# pmic_tps65263_buck.net
KiCad netlist of a schematic drawn in Altium Designer
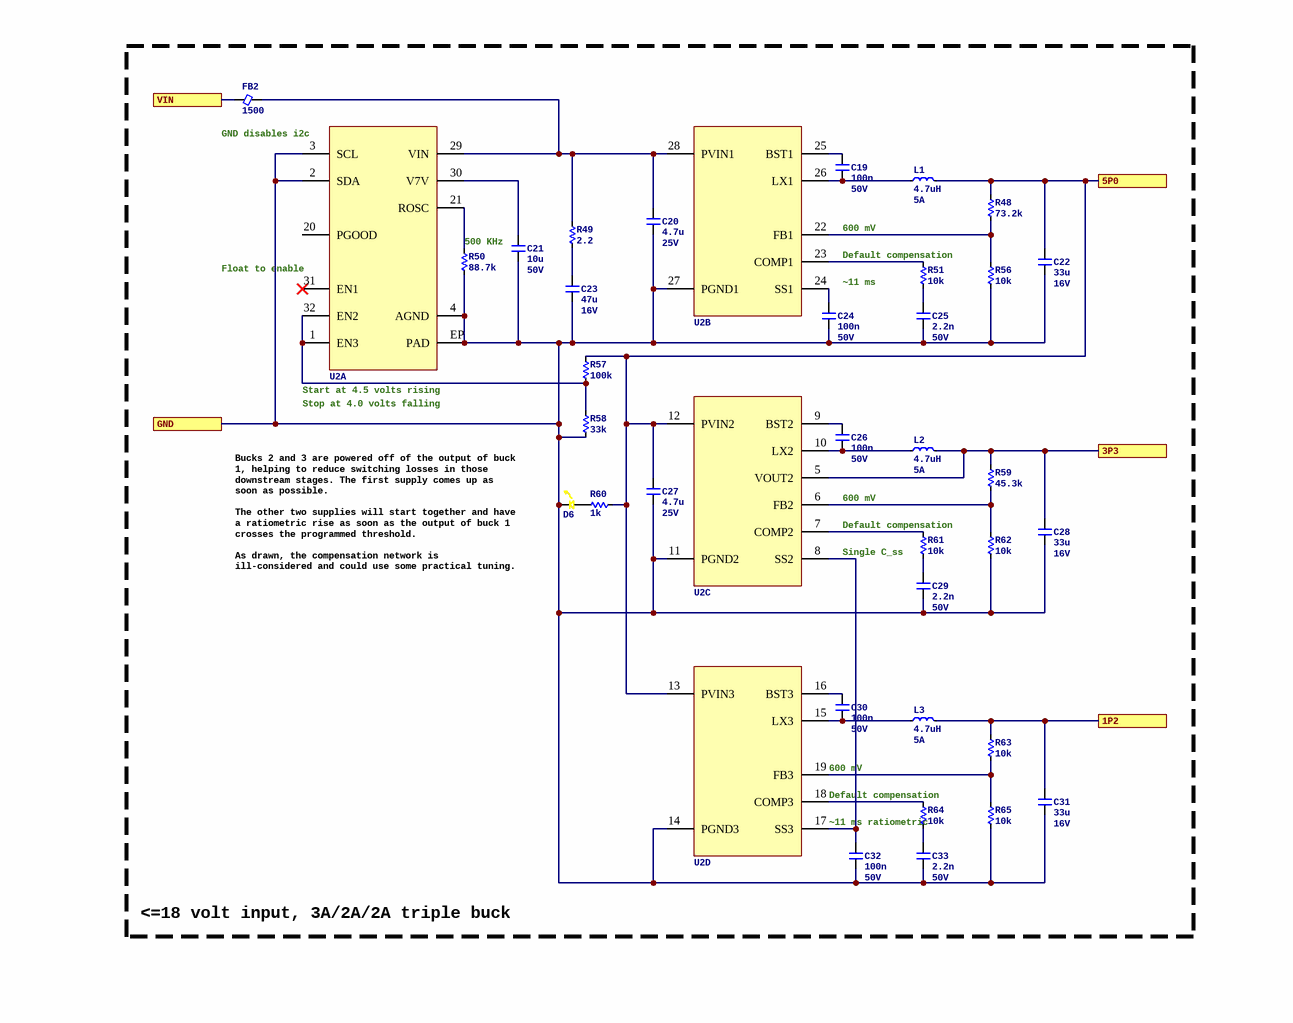
[diagram p0: pmic_tps65263_buck.SchDoc]

(export (version "E")
  (design (tool "Eeschema 10.0.6"))
  (components
    (comp (ref "C19")
      (value "CL05B104KB54PNC")
      (footprint "C0402")
      (fields
        (field (name "CAPACITANCE") "100n")
        (field (name "MANUFACTURER") "Samsung Electro-Mechanics")
        (field (name "VOLTAGE RATING") "50V")
      )
      (libsource (lib "database") (part "__template_cap"))
    )
    (comp (ref "C20")
      (value "CL21B475KAFNNNE")
      (footprint "C0805")
      (fields
        (field (name "CAPACITANCE") "4.7u")
        (field (name "MANUFACTURER") "Samsung Electro-Mechanics")
        (field (name "VOLTAGE RATING") "25V")
      )
      (libsource (lib "database") (part "__template_cap"))
    )
    (comp (ref "C21")
      (value "CL31B106KBHNNNE")
      (footprint "C1206")
      (fields
        (field (name "CAPACITANCE") "10u")
        (field (name "MANUFACTURER") "Samsung Electro-Mechanics")
        (field (name "VOLTAGE RATING") "50V")
      )
      (libsource (lib "database") (part "__template_cap"))
    )
    (comp (ref "C22")
      (value "C4532X7R1C336MT000N")
      (footprint "C1812")
      (fields
        (field (name "CAPACITANCE") "33u")
        (field (name "MANUFACTURER") "TDK")
        (field (name "VOLTAGE RATING") "16V")
      )
      (libsource (lib "database") (part "__template_cap"))
    )
    (comp (ref "C23")
      (value "CGA9N3X7R1C476MT0Y0N")
      (footprint "C2220")
      (fields
        (field (name "CAPACITANCE") "47u")
        (field (name "MANUFACTURER") "TDK")
        (field (name "VOLTAGE RATING") "16V")
      )
      (libsource (lib "database") (part "__template_cap"))
    )
    (comp (ref "C24")
      (value "CL05B104KB54PNC")
      (footprint "C0402")
      (fields
        (field (name "CAPACITANCE") "100n")
        (field (name "MANUFACTURER") "Samsung Electro-Mechanics")
        (field (name "VOLTAGE RATING") "50V")
      )
      (libsource (lib "database") (part "__template_cap"))
    )
    (comp (ref "C25")
      (value "GRM1555C1H222GA01D")
      (footprint "C0402")
      (fields
        (field (name "CAPACITANCE") "2.2n")
        (field (name "MANUFACTURER") "Murata Electronics")
        (field (name "VOLTAGE RATING") "50V")
      )
      (libsource (lib "database") (part "__template_cap"))
    )
    (comp (ref "C26")
      (value "CL05B104KB54PNC")
      (footprint "C0402")
      (fields
        (field (name "CAPACITANCE") "100n")
        (field (name "MANUFACTURER") "Samsung Electro-Mechanics")
        (field (name "VOLTAGE RATING") "50V")
      )
      (libsource (lib "database") (part "__template_cap"))
    )
    (comp (ref "C27")
      (value "CL21B475KAFNNNE")
      (footprint "C0805")
      (fields
        (field (name "CAPACITANCE") "4.7u")
        (field (name "MANUFACTURER") "Samsung Electro-Mechanics")
        (field (name "VOLTAGE RATING") "25V")
      )
      (libsource (lib "database") (part "__template_cap"))
    )
    (comp (ref "C28")
      (value "C4532X7R1C336MT000N")
      (footprint "C1812")
      (fields
        (field (name "CAPACITANCE") "33u")
        (field (name "MANUFACTURER") "TDK")
        (field (name "VOLTAGE RATING") "16V")
      )
      (libsource (lib "database") (part "__template_cap"))
    )
    (comp (ref "C29")
      (value "GRM1555C1H222GA01D")
      (footprint "C0402")
      (fields
        (field (name "CAPACITANCE") "2.2n")
        (field (name "MANUFACTURER") "Murata Electronics")
        (field (name "VOLTAGE RATING") "50V")
      )
      (libsource (lib "database") (part "__template_cap"))
    )
    (comp (ref "C30")
      (value "CL05B104KB54PNC")
      (footprint "C0402")
      (fields
        (field (name "CAPACITANCE") "100n")
        (field (name "MANUFACTURER") "Samsung Electro-Mechanics")
        (field (name "VOLTAGE RATING") "50V")
      )
      (libsource (lib "database") (part "__template_cap"))
    )
    (comp (ref "C31")
      (value "C4532X7R1C336MT000N")
      (footprint "C1812")
      (fields
        (field (name "CAPACITANCE") "33u")
        (field (name "MANUFACTURER") "TDK")
        (field (name "VOLTAGE RATING") "16V")
      )
      (libsource (lib "database") (part "__template_cap"))
    )
    (comp (ref "C32")
      (value "CL05B104KB54PNC")
      (footprint "C0402")
      (fields
        (field (name "CAPACITANCE") "100n")
        (field (name "MANUFACTURER") "Samsung Electro-Mechanics")
        (field (name "VOLTAGE RATING") "50V")
      )
      (libsource (lib "database") (part "__template_cap"))
    )
    (comp (ref "C33")
      (value "GRM1555C1H222GA01D")
      (footprint "C0402")
      (fields
        (field (name "CAPACITANCE") "2.2n")
        (field (name "MANUFACTURER") "Murata Electronics")
        (field (name "VOLTAGE RATING") "50V")
      )
      (libsource (lib "database") (part "__template_cap"))
    )
    (comp (ref "D6")
      (value "LTST-C190YKT")
      (footprint "LED_0603P_YELLOW")
      (description "LED YELLOW CLEAR 0603 SMD")
      (fields (field (name "MANUFACTURER") "Lite-On Inc"))
      (libsource (lib "SSCP") (part "LED_0603_YELLOW_LTST-C190YKT"))
    )
    (comp (ref "FB2")
      (value "MPZ2012S102AT000")
      (footprint "FB0805")
      (fields (field (name "CURRENT RATING (MA)") "1500") (field (name "MANUFACTURER") "TDK"))
      (libsource (lib "database") (part "__template_fb"))
    )
    (comp (ref "L1")
      (value "4.7uH")
      (footprint "SMD-4.1x4.1x2.0")
      (description "5A 4.7uH 6.3A 58mΩ ±20% SMD,4.1x4.1mm Fixed Inductors RoHS")
      (fields
        (field (name "MANUFACTURER PART NUMBER") "FTC404020S4R7MGCA")
        (field (name "MANUFACTURER") "cjiang")
        (field (name "CURRENT") "5A")
      )
      (libsource (lib "SSCP") (part "IND_4.7UH_FTC404020S4R7MGCA"))
    )
    (comp (ref "L2")
      (value "4.7uH")
      (footprint "SMD-4.1x4.1x2.0")
      (description "5A 4.7uH 6.3A 58mΩ ±20% SMD,4.1x4.1mm Fixed Inductors RoHS")
      (fields
        (field (name "MANUFACTURER PART NUMBER") "FTC404020S4R7MGCA")
        (field (name "MANUFACTURER") "cjiang")
        (field (name "CURRENT") "5A")
      )
      (libsource (lib "SSCP") (part "IND_4.7UH_FTC404020S4R7MGCA"))
    )
    (comp (ref "L3")
      (value "4.7uH")
      (footprint "SMD-4.1x4.1x2.0")
      (description "5A 4.7uH 6.3A 58mΩ ±20% SMD,4.1x4.1mm Fixed Inductors RoHS")
      (fields
        (field (name "MANUFACTURER PART NUMBER") "FTC404020S4R7MGCA")
        (field (name "MANUFACTURER") "cjiang")
        (field (name "CURRENT") "5A")
      )
      (libsource (lib "SSCP") (part "IND_4.7UH_FTC404020S4R7MGCA"))
    )
    (comp (ref "R48")
      (value "73.2k")
      (footprint "R0402")
      (fields
        (field (name "TOLERANCE") "1%")
        (field (name "MANUFACTURER PART NUMBER") "0402WGF7322TCE")
        (field (name "MANUFACTURER") "UNI-ROYAL(Uniroyal Elec)")
      )
      (libsource (lib "database") (part "__template_resistor"))
    )
    (comp (ref "R49")
      (value "2.2")
      (footprint "R0805")
      (fields
        (field (name "TOLERANCE") "1%")
        (field (name "MANUFACTURER PART NUMBER") "HP05W3F220KT5E")
        (field (name "MANUFACTURER") "UNI-ROYAL(Uniroyal Elec)")
      )
      (libsource (lib "database") (part "__template_resistor"))
    )
    (comp (ref "R50")
      (value "88.7k")
      (footprint "R0402")
      (fields
        (field (name "TOLERANCE") "1%")
        (field (name "MANUFACTURER PART NUMBER") "0402WGF8872TCE")
        (field (name "MANUFACTURER") "UNI-ROYAL(Uniroyal Elec)")
      )
      (libsource (lib "database") (part "__template_resistor"))
    )
    (comp (ref "R51")
      (value "10k")
      (footprint "R0402")
      (fields
        (field (name "TOLERANCE") "1%")
        (field (name "MANUFACTURER PART NUMBER") "0402WGF1002TCE")
        (field (name "MANUFACTURER") "UNI-ROYAL(Uniroyal Elec)")
      )
      (libsource (lib "database") (part "__template_resistor"))
    )
    (comp (ref "R56")
      (value "10k")
      (footprint "R0402")
      (fields
        (field (name "TOLERANCE") "1%")
        (field (name "MANUFACTURER PART NUMBER") "0402WGF1002TCE")
        (field (name "MANUFACTURER") "UNI-ROYAL(Uniroyal Elec)")
      )
      (libsource (lib "database") (part "__template_resistor"))
    )
    (comp (ref "R57")
      (value "100k")
      (footprint "R0402")
      (fields
        (field (name "TOLERANCE") "1%")
        (field (name "MANUFACTURER PART NUMBER") "0402WGF1003TCE")
        (field (name "MANUFACTURER") "UNI-ROYAL(Uniroyal Elec)")
      )
      (libsource (lib "database") (part "__template_resistor"))
    )
    (comp (ref "R58")
      (value "33k")
      (footprint "R0402")
      (fields
        (field (name "TOLERANCE") "1%")
        (field (name "MANUFACTURER PART NUMBER") "0402WGF3302TCE")
        (field (name "MANUFACTURER") "UNI-ROYAL(Uniroyal Elec)")
      )
      (libsource (lib "database") (part "__template_resistor"))
    )
    (comp (ref "R59")
      (value "45.3k")
      (footprint "R0402")
      (fields
        (field (name "TOLERANCE") "1%")
        (field (name "MANUFACTURER PART NUMBER") "FRC0402F4532TS")
        (field (name "MANUFACTURER") "FOJAN")
      )
      (libsource (lib "database") (part "__template_resistor"))
    )
    (comp (ref "R60")
      (value "1k")
      (footprint "R0402")
      (fields
        (field (name "TOLERANCE") "1%")
        (field (name "MANUFACTURER PART NUMBER") "0402WGF1001TCE")
        (field (name "MANUFACTURER") "UNI-ROYAL(Uniroyal Elec)")
      )
      (libsource (lib "database") (part "__template_resistor"))
    )
    (comp (ref "R61")
      (value "10k")
      (footprint "R0402")
      (fields
        (field (name "TOLERANCE") "1%")
        (field (name "MANUFACTURER PART NUMBER") "0402WGF1002TCE")
        (field (name "MANUFACTURER") "UNI-ROYAL(Uniroyal Elec)")
      )
      (libsource (lib "database") (part "__template_resistor"))
    )
    (comp (ref "R62")
      (value "10k")
      (footprint "R0402")
      (fields
        (field (name "TOLERANCE") "1%")
        (field (name "MANUFACTURER PART NUMBER") "0402WGF1002TCE")
        (field (name "MANUFACTURER") "UNI-ROYAL(Uniroyal Elec)")
      )
      (libsource (lib "database") (part "__template_resistor"))
    )
    (comp (ref "R63")
      (value "10k")
      (footprint "R0402")
      (fields
        (field (name "TOLERANCE") "1%")
        (field (name "MANUFACTURER PART NUMBER") "0402WGF1002TCE")
        (field (name "MANUFACTURER") "UNI-ROYAL(Uniroyal Elec)")
      )
      (libsource (lib "database") (part "__template_resistor"))
    )
    (comp (ref "R64")
      (value "10k")
      (footprint "R0402")
      (fields
        (field (name "TOLERANCE") "1%")
        (field (name "MANUFACTURER PART NUMBER") "0402WGF1002TCE")
        (field (name "MANUFACTURER") "UNI-ROYAL(Uniroyal Elec)")
      )
      (libsource (lib "database") (part "__template_resistor"))
    )
    (comp (ref "R65")
      (value "10k")
      (footprint "R0402")
      (fields
        (field (name "TOLERANCE") "1%")
        (field (name "MANUFACTURER PART NUMBER") "0402WGF1002TCE")
        (field (name "MANUFACTURER") "UNI-ROYAL(Uniroyal Elec)")
      )
      (libsource (lib "database") (part "__template_resistor"))
    )
    (comp (ref "U2")
      (value "TPS65263QRHBRQ1")
      (footprint "TI_RHB")
      (description "Switching Regulator, Current-mode, 3A, 2300kHz Switching Freq-Max, PQCC32")
      (fields (field (name "MANUFACTURER") "Texas Instruments"))
      (libsource (lib "SSCP") (part "BUCK_TPS65263QRHBRQ1"))
    )
  )
  (nets
    (net (code "1") (name "/1P2") (class "Default")
      (node (ref "C31") (pin "1") (pintype "passive"))
      (node (ref "L3") (pin "2") (pintype "passive"))
      (node (ref "R63") (pin "2") (pintype "passive"))
    )
    (net (code "2") (name "/3P3") (class "Default")
      (node (ref "C28") (pin "1") (pintype "passive"))
      (node (ref "L2") (pin "2") (pintype "passive"))
      (node (ref "R59") (pin "2") (pintype "passive"))
      (node (ref "U2") (pin "5") (pinfunction "VOUT2_5") (pintype "passive"))
    )
    (net (code "3") (name "/5P0") (class "Default")
      (node (ref "C22") (pin "1") (pintype "passive"))
      (node (ref "C27") (pin "1") (pintype "passive"))
      (node (ref "L1") (pin "2") (pintype "passive"))
      (node (ref "R48") (pin "2") (pintype "passive"))
      (node (ref "R57") (pin "2") (pintype "passive"))
      (node (ref "R60") (pin "2") (pintype "passive"))
      (node (ref "U2") (pin "12") (pinfunction "PVIN2_12") (pintype "passive"))
      (node (ref "U2") (pin "13") (pinfunction "PVIN3_13") (pintype "passive"))
    )
    (net (code "4") (name "/GND") (class "Default")
      (node (ref "C20") (pin "2") (pintype "passive"))
      (node (ref "C21") (pin "2") (pintype "passive"))
      (node (ref "C22") (pin "2") (pintype "passive"))
      (node (ref "C23") (pin "2") (pintype "passive"))
      (node (ref "C24") (pin "2") (pintype "passive"))
      (node (ref "C25") (pin "2") (pintype "passive"))
      (node (ref "C27") (pin "2") (pintype "passive"))
      (node (ref "C28") (pin "2") (pintype "passive"))
      (node (ref "C29") (pin "2") (pintype "passive"))
      (node (ref "C31") (pin "2") (pintype "passive"))
      (node (ref "C32") (pin "2") (pintype "passive"))
      (node (ref "C33") (pin "2") (pintype "passive"))
      (node (ref "D6") (pin "1") (pintype "passive"))
      (node (ref "R50") (pin "1") (pintype "passive"))
      (node (ref "R56") (pin "1") (pintype "passive"))
      (node (ref "R58") (pin "1") (pintype "passive"))
      (node (ref "R62") (pin "1") (pintype "passive"))
      (node (ref "R65") (pin "1") (pintype "passive"))
      (node (ref "U2") (pin "11") (pinfunction "PGND2_11") (pintype "passive"))
      (node (ref "U2") (pin "14") (pinfunction "PGND3_14") (pintype "passive"))
      (node (ref "U2") (pin "2") (pinfunction "SDA_2") (pintype "passive"))
      (node (ref "U2") (pin "27") (pinfunction "PGND1_27") (pintype "passive"))
      (node (ref "U2") (pin "3") (pinfunction "SCL_3") (pintype "passive"))
      (node (ref "U2") (pin "4") (pinfunction "AGND_4") (pintype "passive"))
      (node (ref "U2") (pin "EP") (pinfunction "PAD_EP") (pintype "passive"))
    )
    (net (code "5") (name "/VIN") (class "Default") (node (ref "FB2") (pin "1") (pintype "passive")))
    (net (code "6") (name "Net-(C23-Pad1)") (class "Default")
      (node (ref "C23") (pin "1") (pintype "passive"))
      (node (ref "R49") (pin "1") (pintype "passive"))
    )
    (net (code "7") (name "Net-(C25-Pad1)") (class "Default")
      (node (ref "C25") (pin "1") (pintype "passive"))
      (node (ref "R51") (pin "1") (pintype "passive"))
    )
    (net (code "8") (name "Net-(C29-Pad1)") (class "Default")
      (node (ref "C29") (pin "1") (pintype "passive"))
      (node (ref "R61") (pin "1") (pintype "passive"))
    )
    (net (code "9") (name "Net-(C33-Pad1)") (class "Default")
      (node (ref "C33") (pin "1") (pintype "passive"))
      (node (ref "R64") (pin "1") (pintype "passive"))
    )
    (net (code "10") (name "Net-(D6-Pad2)") (class "Default")
      (node (ref "D6") (pin "2") (pintype "passive"))
      (node (ref "R60") (pin "1") (pintype "passive"))
    )
    (net (code "11") (name "Net-(U2A-EN2)") (class "Default")
      (node (ref "R57") (pin "1") (pintype "passive"))
      (node (ref "R58") (pin "2") (pintype "passive"))
      (node (ref "U2") (pin "1") (pinfunction "EN3_1") (pintype "passive"))
      (node (ref "U2") (pin "32") (pinfunction "EN2_32") (pintype "passive"))
    )
    (net (code "12") (name "Net-(U2A-ROSC)") (class "Default")
      (node (ref "R50") (pin "2") (pintype "passive"))
      (node (ref "U2") (pin "21") (pinfunction "ROSC_21") (pintype "passive"))
    )
    (net (code "13") (name "Net-(U2A-V7V)") (class "Default")
      (node (ref "C21") (pin "1") (pintype "passive"))
      (node (ref "U2") (pin "30") (pinfunction "V7V_30") (pintype "passive"))
    )
    (net (code "14") (name "Net-(U2A-VIN)") (class "Default")
      (node (ref "C20") (pin "1") (pintype "passive"))
      (node (ref "FB2") (pin "2") (pintype "passive"))
      (node (ref "R49") (pin "2") (pintype "passive"))
      (node (ref "U2") (pin "28") (pinfunction "PVIN1_28") (pintype "passive"))
      (node (ref "U2") (pin "29") (pinfunction "VIN_29") (pintype "passive"))
    )
    (net (code "15") (name "Net-(U2B-BST1)") (class "Default")
      (node (ref "C19") (pin "1") (pintype "passive"))
      (node (ref "U2") (pin "25") (pinfunction "BST1_25") (pintype "passive"))
    )
    (net (code "16") (name "Net-(U2B-COMP1)") (class "Default")
      (node (ref "R51") (pin "2") (pintype "passive"))
      (node (ref "U2") (pin "23") (pinfunction "COMP1_23") (pintype "passive"))
    )
    (net (code "17") (name "Net-(U2B-FB1)") (class "Default")
      (node (ref "R48") (pin "1") (pintype "passive"))
      (node (ref "R56") (pin "2") (pintype "passive"))
      (node (ref "U2") (pin "22") (pinfunction "FB1_22") (pintype "passive"))
    )
    (net (code "18") (name "Net-(U2B-LX1)") (class "Default")
      (node (ref "C19") (pin "2") (pintype "passive"))
      (node (ref "L1") (pin "1") (pintype "passive"))
      (node (ref "U2") (pin "26") (pinfunction "LX1_26") (pintype "passive"))
    )
    (net (code "19") (name "Net-(U2B-SS1)") (class "Default")
      (node (ref "C24") (pin "1") (pintype "passive"))
      (node (ref "U2") (pin "24") (pinfunction "SS1_24") (pintype "passive"))
    )
    (net (code "20") (name "Net-(U2C-BST2)") (class "Default")
      (node (ref "C26") (pin "1") (pintype "passive"))
      (node (ref "U2") (pin "9") (pinfunction "BST2_9") (pintype "passive"))
    )
    (net (code "21") (name "Net-(U2C-COMP2)") (class "Default")
      (node (ref "R61") (pin "2") (pintype "passive"))
      (node (ref "U2") (pin "7") (pinfunction "COMP2_7") (pintype "passive"))
    )
    (net (code "22") (name "Net-(U2C-FB2)") (class "Default")
      (node (ref "R59") (pin "1") (pintype "passive"))
      (node (ref "R62") (pin "2") (pintype "passive"))
      (node (ref "U2") (pin "6") (pinfunction "FB2_6") (pintype "passive"))
    )
    (net (code "23") (name "Net-(U2C-LX2)") (class "Default")
      (node (ref "C26") (pin "2") (pintype "passive"))
      (node (ref "L2") (pin "1") (pintype "passive"))
      (node (ref "U2") (pin "10") (pinfunction "LX2_10") (pintype "passive"))
    )
    (net (code "24") (name "Net-(U2C-SS2)") (class "Default")
      (node (ref "C32") (pin "1") (pintype "passive"))
      (node (ref "U2") (pin "17") (pinfunction "SS3_17") (pintype "passive"))
      (node (ref "U2") (pin "8") (pinfunction "SS2_8") (pintype "passive"))
    )
    (net (code "25") (name "Net-(U2D-BST3)") (class "Default")
      (node (ref "C30") (pin "1") (pintype "passive"))
      (node (ref "U2") (pin "16") (pinfunction "BST3_16") (pintype "passive"))
    )
    (net (code "26") (name "Net-(U2D-COMP3)") (class "Default")
      (node (ref "R64") (pin "2") (pintype "passive"))
      (node (ref "U2") (pin "18") (pinfunction "COMP3_18") (pintype "passive"))
    )
    (net (code "27") (name "Net-(U2D-FB3)") (class "Default")
      (node (ref "R63") (pin "1") (pintype "passive"))
      (node (ref "R65") (pin "2") (pintype "passive"))
      (node (ref "U2") (pin "19") (pinfunction "FB3_19") (pintype "passive"))
    )
    (net (code "28") (name "Net-(U2D-LX3)") (class "Default")
      (node (ref "C30") (pin "2") (pintype "passive"))
      (node (ref "L3") (pin "1") (pintype "passive"))
      (node (ref "U2") (pin "15") (pinfunction "LX3_15") (pintype "passive"))
    )
    (net (code "29") (name "unconnected-(U2A-EN1-Pad31)") (class "Default")
      (node (ref "U2") (pin "31") (pinfunction "EN1_31") (pintype "passive+no_connect"))
    )
    (net (code "30") (name "unconnected-(U2A-PGOOD-Pad20)") (class "Default")
      (node (ref "U2") (pin "20") (pinfunction "PGOOD_20") (pintype "passive"))
    )
  )
)
